# ATMega32U4-CC3000.net
KiCad netlist of a schematic drawn in EAGLE
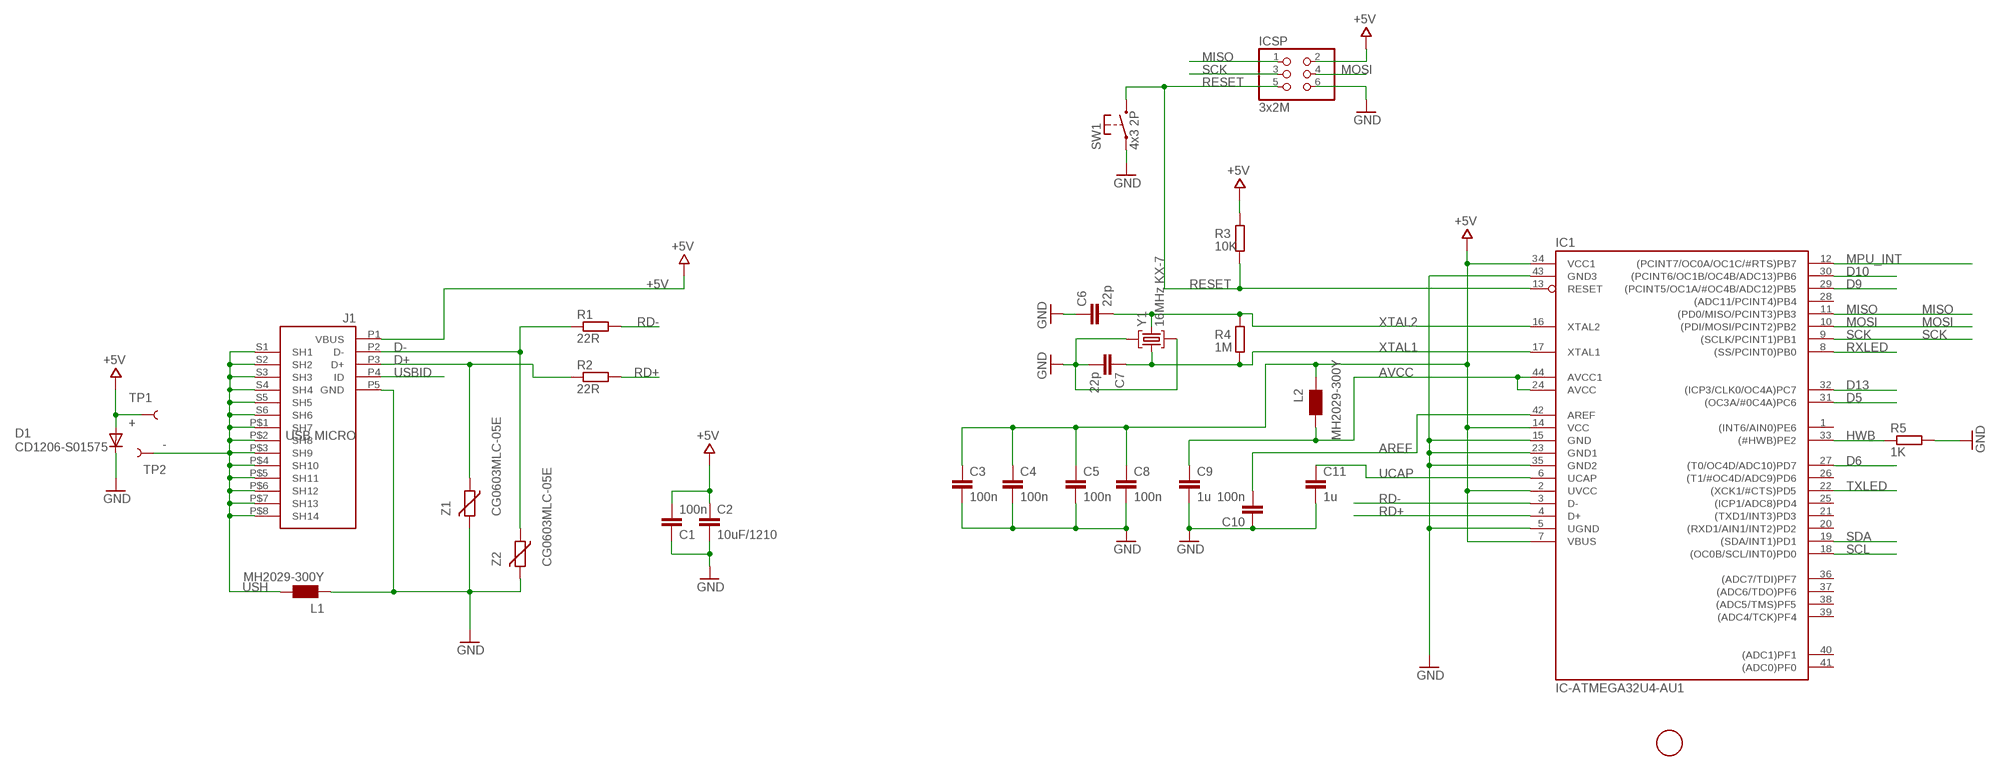
[diagram p0: schematic, sheet 1, part 1 of 2]
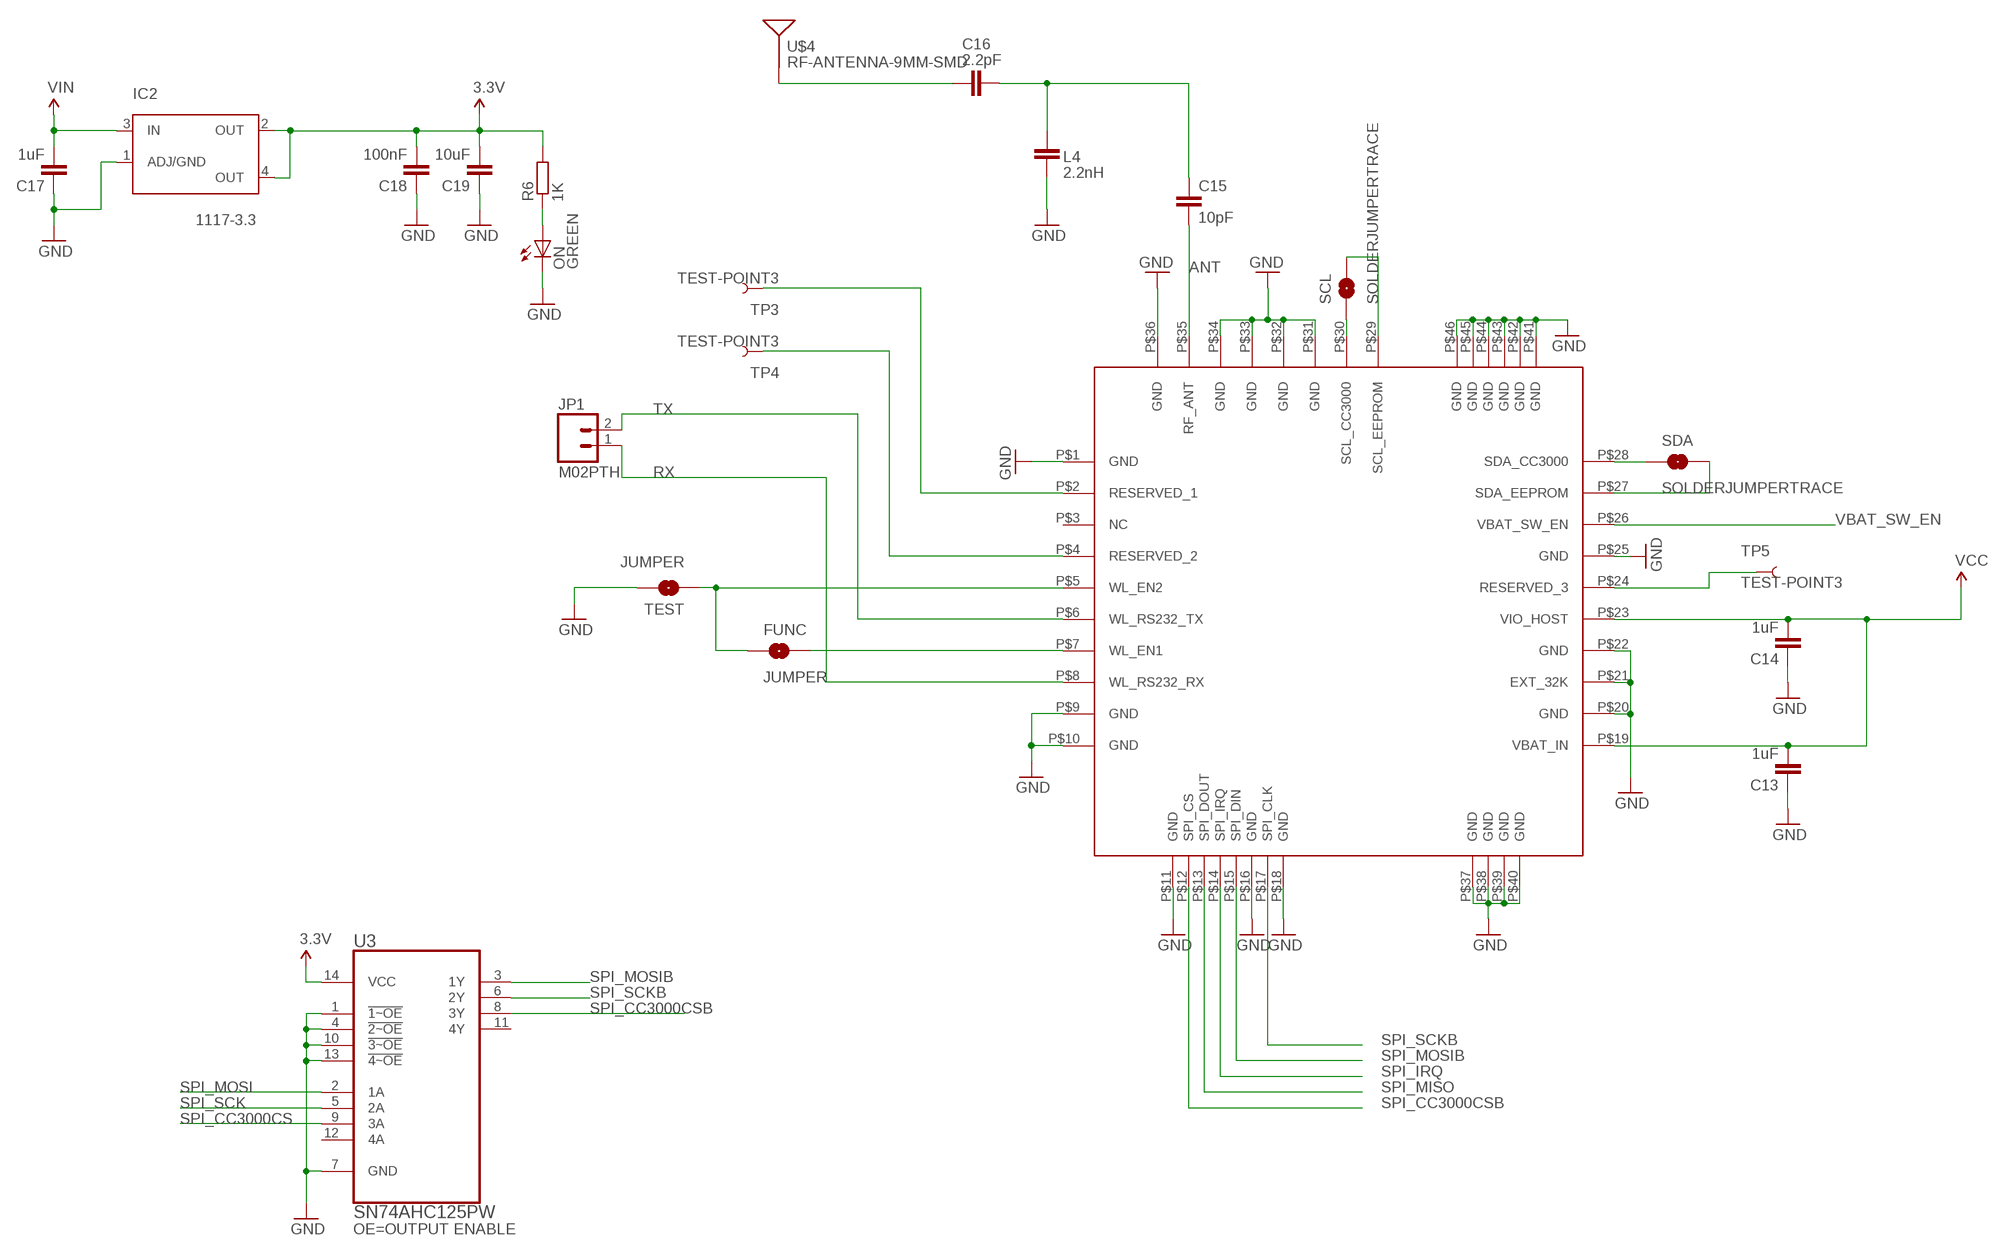
[diagram p1: schematic, sheet 1, part 2 of 2]

(export (version "E")
  (design (tool "Eeschema 10.0.6"))
  (components
    (comp (ref "C1")
      (value "100n")
      (footprint "eagle-import:C0603-ROUND")
      (libsource (lib "eagle-import") (part "C-EUC0603"))
    )
    (comp (ref "C2")
      (value "10uF/1210")
      (footprint "eagle-import:CAP-1210_SMC-B-SMT")
      (libsource (lib "eagle-import") (part "CAPACITOR1210"))
    )
    (comp (ref "C3")
      (value "100n")
      (footprint "eagle-import:CAP-0402-SMT-ROUND")
      (libsource (lib "eagle-import") (part "CAPACITOR0402"))
    )
    (comp (ref "C4")
      (value "100n")
      (footprint "eagle-import:CAP-0402-SMT-ROUND")
      (libsource (lib "eagle-import") (part "CAPACITOR0402"))
    )
    (comp (ref "C5")
      (value "100n")
      (footprint "eagle-import:CAP-0402-SMT-ROUND")
      (libsource (lib "eagle-import") (part "CAPACITOR0402"))
    )
    (comp (ref "C6")
      (value "22p")
      (footprint "eagle-import:CAP-0402-SMT-ROUND")
      (libsource (lib "eagle-import") (part "CAPACITOR0402"))
    )
    (comp (ref "C7")
      (value "22p")
      (footprint "eagle-import:CAP-0402-SMT-ROUND")
      (libsource (lib "eagle-import") (part "CAPACITOR0402"))
    )
    (comp (ref "C8")
      (value "100n")
      (footprint "eagle-import:CAP-0402-SMT-ROUND")
      (libsource (lib "eagle-import") (part "CAPACITOR0402"))
    )
    (comp (ref "C9")
      (value "1u")
      (footprint "eagle-import:CAP-0402-SMT-ROUND")
      (libsource (lib "eagle-import") (part "CAPACITOR0402"))
    )
    (comp (ref "C10")
      (value "100n")
      (footprint "eagle-import:CAP-0402-SMT-ROUND")
      (libsource (lib "eagle-import") (part "CAPACITOR0402"))
    )
    (comp (ref "C11")
      (value "1u")
      (footprint "eagle-import:CAP-0402-SMT-ROUND")
      (libsource (lib "eagle-import") (part "CAPACITOR0402"))
    )
    (comp (ref "C13")
      (value "1uF")
      (footprint "eagle-import:CAP-0603-SMT-ROUND")
      (libsource (lib "eagle-import") (part "CAPACITOR0603"))
    )
    (comp (ref "C14")
      (value "1uF")
      (footprint "eagle-import:CAP-0603-SMT-ROUND")
      (libsource (lib "eagle-import") (part "CAPACITOR0603"))
    )
    (comp (ref "C15")
      (value "10pF")
      (footprint "eagle-import:CAP-0603-SMT-ROUND")
      (libsource (lib "eagle-import") (part "CAPACITOR0603"))
    )
    (comp (ref "C16")
      (value "2.2pF")
      (footprint "eagle-import:CAP-0603-SMT-ROUND")
      (libsource (lib "eagle-import") (part "CAPACITOR0603"))
    )
    (comp (ref "C17")
      (value "1uF")
      (footprint "eagle-import:CAP-0603-SMT-ROUND")
      (libsource (lib "eagle-import") (part "CAPACITOR0603"))
    )
    (comp (ref "C18")
      (value "100nF")
      (footprint "eagle-import:CAP-0603-SMT-ROUND")
      (libsource (lib "eagle-import") (part "CAPACITOR0603"))
    )
    (comp (ref "C19")
      (value "10uF")
      (footprint "eagle-import:CAP-1210_SMC-B-SMT")
      (libsource (lib "eagle-import") (part "CAPACITOR1210"))
    )
    (comp (ref "D1")
      (value "CD1206-S01575")
      (footprint "eagle-import:DIODE-1206-SMT")
      (libsource (lib "eagle-import") (part "DIODE-SWITCHINGCD1206-S01575"))
    )
    (comp (ref "FID1")
      (value "FIDUCIALMOUNT")
      (footprint "eagle-import:FIDUCIA-MOUNT")
      (libsource (lib "eagle-import") (part "FIDUCIALMOUNT"))
    )
    (comp (ref "FUNC")
      (value "JUMPER")
      (footprint "eagle-import:SJ_2S-TRACE")
      (libsource (lib "eagle-import") (part "SparkFun-Passives_SOLDERJUMPERTRACE"))
    )
    (comp (ref "IC1")
      (value "IC-ATMEGA32U4-AU1")
      (footprint "eagle-import:QFP-10X10-44P")
      (libsource (lib "eagle-import") (part "IC-ATMEGA32U4-AU1"))
    )
    (comp (ref "IC2")
      (value "1117-3.3")
      (footprint "eagle-import:LDO-SOT223")
      (libsource (lib "eagle-import") (part "LDO-AMS1117-X"))
    )
    (comp (ref "ICSP")
      (value "3x2M")
      (footprint "eagle-import:2X03")
      (libsource (lib "eagle-import") (part "PINHD-2X3"))
    )
    (comp (ref "J1")
      (value "USB MICRO")
      (footprint "eagle-import:CON2_USB_MICRO_B_AT")
      (libsource (lib "eagle-import") (part "MYCON2_USB-MINI-B"))
    )
    (comp (ref "JP1")
      (value "M02PTH")
      (footprint "eagle-import:1X02")
      (libsource (lib "eagle-import") (part "M02PTH"))
    )
    (comp (ref "L1")
      (value "MH2029-300Y")
      (footprint "eagle-import:0805")
      (libsource (lib "eagle-import") (part "WE-CBF_0805"))
    )
    (comp (ref "L2")
      (value "MH2029-300Y")
      (footprint "eagle-import:0805")
      (libsource (lib "eagle-import") (part "WE-CBF_0805"))
    )
    (comp (ref "L4")
      (value "2.2nH")
      (footprint "eagle-import:CAP-0603-SMT-ROUND")
      (libsource (lib "eagle-import") (part "CAPACITOR0603"))
    )
    (comp (ref "ON")
      (value "GREEN")
      (footprint "eagle-import:LED-0805-SMT")
      (libsource (lib "eagle-import") (part "DIODE-LED0805"))
    )
    (comp (ref "R1")
      (value "22R")
      (footprint "eagle-import:RESISTOR-0402-SMT-ROUND")
      (libsource (lib "eagle-import") (part "RESISTOR0402"))
    )
    (comp (ref "R2")
      (value "22R")
      (footprint "eagle-import:RESISTOR-0402-SMT-ROUND")
      (libsource (lib "eagle-import") (part "RESISTOR0402"))
    )
    (comp (ref "R3")
      (value "10K")
      (footprint "eagle-import:RESISTOR-0402-SMT-ROUND")
      (libsource (lib "eagle-import") (part "RESISTOR0402"))
    )
    (comp (ref "R4")
      (value "1M")
      (footprint "eagle-import:RESISTOR-0402-SMT-ROUND")
      (libsource (lib "eagle-import") (part "RESISTOR0402"))
    )
    (comp (ref "R5")
      (value "1K")
      (footprint "eagle-import:RESISTOR-0402-SMT-ROUND")
      (libsource (lib "eagle-import") (part "RESISTOR0402"))
    )
    (comp (ref "R6")
      (value "1K")
      (footprint "eagle-import:RESISTOR-0603-SMT-ROUND")
      (libsource (lib "eagle-import") (part "RESISTOR0603"))
    )
    (comp (ref "SCL")
      (value "SOLDERJUMPERTRACE")
      (footprint "eagle-import:SJ_2S-TRACE")
      (libsource (lib "eagle-import") (part "SparkFun-Passives_SOLDERJUMPERTRACE"))
    )
    (comp (ref "SDA")
      (value "SOLDERJUMPERTRACE")
      (footprint "eagle-import:SJ_2S-TRACE")
      (libsource (lib "eagle-import") (part "SparkFun-Passives_SOLDERJUMPERTRACE"))
    )
    (comp (ref "SW1")
      (value "4x3 2P")
      (footprint "eagle-import:SWITCH-2.1-SMT")
      (libsource (lib "eagle-import") (part "SWITCH-2P2.1-SMT"))
    )
    (comp (ref "TEST")
      (value "JUMPER")
      (footprint "eagle-import:SJ_2S-NO")
      (libsource (lib "eagle-import") (part "SOLDERJUMPERNO"))
    )
    (comp (ref "TP1")
      (value "+")
      (footprint "eagle-import:PAD.03X.05")
      (libsource (lib "eagle-import") (part "TEST-POINT3X5"))
    )
    (comp (ref "TP2")
      (value "-")
      (footprint "eagle-import:PAD.03X.05")
      (libsource (lib "eagle-import") (part "TEST-POINT3X5"))
    )
    (comp (ref "TP3")
      (value "TEST-POINT3")
      (footprint "eagle-import:PAD.03X.03")
      (libsource (lib "eagle-import") (part "TEST-POINT3"))
    )
    (comp (ref "TP4")
      (value "TEST-POINT3")
      (footprint "eagle-import:PAD.03X.03")
      (libsource (lib "eagle-import") (part "TEST-POINT3"))
    )
    (comp (ref "TP5")
      (value "TEST-POINT3")
      (footprint "eagle-import:PAD.03X.03")
      (libsource (lib "eagle-import") (part "TEST-POINT3"))
    )
    (comp (ref "U$4")
      (value "RF-ANTENNA-9MM-SMD")
      (footprint "eagle-import:RF-ANTENNA-9MM")
      (libsource (lib "eagle-import") (part "RF-ANTENNA-9MM-SMD"))
    )
    (comp (ref "U1")
      (value "CC3000")
      (footprint "eagle-import:CC3000")
      (fields (field (name "AUTHOR") "Matt Bigarani"))
      (libsource (lib "eagle-import") (part "CC3000"))
    )
    (comp (ref "U3")
      (value "SN74AHC125PW")
      (footprint "eagle-import:SOP65P640X120-14N")
      (libsource (lib "eagle-import") (part "IC-TI-SN74AHC125PW"))
    )
    (comp (ref "Y1")
      (value "16MHz KX-7")
      (footprint "eagle-import:CRYSTAL-3.2-2.5")
      (libsource (lib "eagle-import") (part "CRYSTAL-3.2-2.5"))
    )
    (comp (ref "Z1")
      (value "CG0603MLC-05E")
      (footprint "eagle-import:CT_CN0603")
      (libsource (lib "eagle-import") (part "VARISTORCN0603"))
    )
    (comp (ref "Z2")
      (value "CG0603MLC-05E")
      (footprint "eagle-import:CT_CN0603")
      (libsource (lib "eagle-import") (part "VARISTORCN0603"))
    )
  )
  (nets
    (net (code "1") (name "+5V") (class "Default")
      (node (ref "C1") (pin "2") (pinfunction "2_2") (pintype "passive"))
      (node (ref "C2") (pin "+") (pinfunction "1_+") (pintype "passive"))
      (node (ref "C3") (pin "1") (pinfunction "1_1") (pintype "passive"))
      (node (ref "C4") (pin "1") (pinfunction "1_1") (pintype "passive"))
      (node (ref "C5") (pin "1") (pinfunction "1_1") (pintype "passive"))
      (node (ref "C8") (pin "1") (pinfunction "1_1") (pintype "passive"))
      (node (ref "D1") (pin "A") (pinfunction "A_A") (pintype "passive"))
      (node (ref "IC1") (pin "14") (pinfunction "VCC_14") (pintype "power_in"))
      (node (ref "IC1") (pin "2") (pinfunction "UVCC_2") (pintype "power_in"))
      (node (ref "IC1") (pin "34") (pinfunction "VCC1_34") (pintype "power_in"))
      (node (ref "IC1") (pin "7") (pinfunction "VBUS_7") (pintype "input"))
      (node (ref "ICSP") (pin "2") (pinfunction "2_2") (pintype "passive"))
      (node (ref "J1") (pin "P1") (pinfunction "VBUS_P1") (pintype "power_in"))
      (node (ref "L2") (pin "1") (pinfunction "1_1") (pintype "passive"))
      (node (ref "R3") (pin "1") (pinfunction "1_1") (pintype "passive"))
      (node (ref "TP1") (pin "P$1") (pinfunction "1_P$1") (pintype "bidirectional"))
    )
    (net (code "2") (name "/ANT") (class "Default")
      (node (ref "C15") (pin "2") (pinfunction "2_2") (pintype "passive"))
      (node (ref "U1") (pin "P$35") (pinfunction "RF_ANT_P$35") (pintype "bidirectional"))
    )
    (net (code "3") (name "/AREF") (class "Default")
      (node (ref "C10") (pin "2") (pinfunction "2_2") (pintype "passive"))
      (node (ref "IC1") (pin "42") (pinfunction "AREF_42") (pintype "power_in"))
    )
    (net (code "4") (name "/AVCC") (class "Default")
      (node (ref "C9") (pin "1") (pinfunction "1_1") (pintype "passive"))
      (node (ref "IC1") (pin "24") (pinfunction "AVCC_24") (pintype "power_in"))
      (node (ref "IC1") (pin "44") (pinfunction "AVCC1_44") (pintype "power_in"))
      (node (ref "L2") (pin "2") (pinfunction "2_2") (pintype "passive"))
    )
    (net (code "5") (name "/D+") (class "Default")
      (node (ref "J1") (pin "P3") (pinfunction "D+_P3") (pintype "bidirectional"))
      (node (ref "R2") (pin "1") (pinfunction "1_1") (pintype "passive"))
      (node (ref "Z1") (pin "1") (pinfunction "1_1") (pintype "passive"))
    )
    (net (code "6") (name "/D-") (class "Default")
      (node (ref "J1") (pin "P2") (pinfunction "D-_P2") (pintype "bidirectional"))
      (node (ref "R1") (pin "1") (pinfunction "1_1") (pintype "passive"))
      (node (ref "Z2") (pin "1") (pinfunction "1_1") (pintype "passive"))
    )
    (net (code "7") (name "/D5") (class "Default")
      (node (ref "IC1") (pin "31") (pinfunction "(OC3A/#0C4A)PC6_31") (pintype "bidirectional"))
    )
    (net (code "8") (name "/D6") (class "Default")
      (node (ref "IC1") (pin "27") (pinfunction "(T0/OC4D/ADC10)PD7_27") (pintype "bidirectional"))
    )
    (net (code "9") (name "/D9") (class "Default")
      (node (ref "IC1") (pin "29") (pinfunction "(PCINT5/OC1A/#OC4B/ADC12)PB5_29") (pintype "bidirectional"))
    )
    (net (code "10") (name "/D10") (class "Default")
      (node (ref "IC1") (pin "30") (pinfunction "(PCINT6/OC1B/OC4B/ADC13)PB6_30") (pintype "bidirectional"))
    )
    (net (code "11") (name "/D13") (class "Default")
      (node (ref "IC1") (pin "32") (pinfunction "(ICP3/CLK0/OC4A)PC7_32") (pintype "bidirectional"))
    )
    (net (code "12") (name "/HWB") (class "Default")
      (node (ref "IC1") (pin "33") (pinfunction "(#HWB)PE2_33") (pintype "bidirectional"))
      (node (ref "R5") (pin "1") (pinfunction "1_1") (pintype "passive"))
    )
    (net (code "13") (name "/MISO") (class "Default")
      (node (ref "IC1") (pin "11") (pinfunction "(PD0/MISO/PCINT3)PB3_11") (pintype "bidirectional"))
      (node (ref "ICSP") (pin "1") (pinfunction "1_1") (pintype "passive"))
    )
    (net (code "14") (name "/MOSI") (class "Default")
      (node (ref "IC1") (pin "10") (pinfunction "(PDI/MOSI/PCINT2)PB2_10") (pintype "bidirectional"))
      (node (ref "ICSP") (pin "4") (pinfunction "4_4") (pintype "passive"))
    )
    (net (code "15") (name "/MPU_INT") (class "Default")
      (node (ref "IC1") (pin "12") (pinfunction "(PCINT7/OC0A/OC1C/#RTS)PB7_12") (pintype "bidirectional"))
    )
    (net (code "16") (name "/RD+") (class "Default")
      (node (ref "IC1") (pin "4") (pinfunction "D+_4") (pintype "bidirectional"))
      (node (ref "R2") (pin "2") (pinfunction "2_2") (pintype "passive"))
    )
    (net (code "17") (name "/RD-") (class "Default")
      (node (ref "IC1") (pin "3") (pinfunction "D-_3") (pintype "bidirectional"))
      (node (ref "R1") (pin "2") (pinfunction "2_2") (pintype "passive"))
    )
    (net (code "18") (name "/RESET") (class "Default")
      (node (ref "IC1") (pin "13") (pinfunction "RESET_13") (pintype "input"))
      (node (ref "ICSP") (pin "5") (pinfunction "5_5") (pintype "passive"))
      (node (ref "R3") (pin "2") (pinfunction "2_2") (pintype "passive"))
      (node (ref "SW1") (pin "2") (pinfunction "2_2") (pintype "passive"))
    )
    (net (code "19") (name "/RX") (class "Default")
      (node (ref "JP1") (pin "1") (pinfunction "1_1") (pintype "passive"))
      (node (ref "U1") (pin "P$8") (pinfunction "WL_RS232_RX_P$8") (pintype "bidirectional"))
    )
    (net (code "20") (name "/RXLED") (class "Default")
      (node (ref "IC1") (pin "8") (pinfunction "(SS/PCINT0)PB0_8") (pintype "bidirectional"))
    )
    (net (code "21") (name "/SCK") (class "Default")
      (node (ref "IC1") (pin "9") (pinfunction "(SCLK/PCINT1)PB1_9") (pintype "bidirectional"))
      (node (ref "ICSP") (pin "3") (pinfunction "3_3") (pintype "passive"))
    )
    (net (code "22") (name "/SCL") (class "Default")
      (node (ref "IC1") (pin "18") (pinfunction "(OC0B/SCL/INT0)PD0_18") (pintype "bidirectional"))
    )
    (net (code "23") (name "/SDA") (class "Default")
      (node (ref "IC1") (pin "19") (pinfunction "(SDA/INT1)PD1_19") (pintype "bidirectional"))
    )
    (net (code "24") (name "/SPI_CC3000CS") (class "Default")
      (node (ref "U3") (pin "9") (pinfunction "3A_9") (pintype "input"))
    )
    (net (code "25") (name "/SPI_CC3000CSB") (class "Default")
      (node (ref "U1") (pin "P$12") (pinfunction "SPI_CS_P$12") (pintype "bidirectional"))
      (node (ref "U3") (pin "8") (pinfunction "3Y_8") (pintype "output"))
    )
    (net (code "26") (name "/SPI_IRQ") (class "Default")
      (node (ref "U1") (pin "P$14") (pinfunction "SPI_IRQ_P$14") (pintype "bidirectional"))
    )
    (net (code "27") (name "/SPI_MISO") (class "Default")
      (node (ref "U1") (pin "P$13") (pinfunction "SPI_DOUT_P$13") (pintype "bidirectional"))
    )
    (net (code "28") (name "/SPI_MOSI") (class "Default")
      (node (ref "U3") (pin "2") (pinfunction "1A_2") (pintype "input"))
    )
    (net (code "29") (name "/SPI_MOSIB") (class "Default")
      (node (ref "U1") (pin "P$15") (pinfunction "SPI_DIN_P$15") (pintype "bidirectional"))
      (node (ref "U3") (pin "3") (pinfunction "1Y_3") (pintype "output"))
    )
    (net (code "30") (name "/SPI_SCK") (class "Default")
      (node (ref "U3") (pin "5") (pinfunction "2A_5") (pintype "input"))
    )
    (net (code "31") (name "/SPI_SCKB") (class "Default")
      (node (ref "U1") (pin "P$17") (pinfunction "SPI_CLK_P$17") (pintype "bidirectional"))
      (node (ref "U3") (pin "6") (pinfunction "2Y_6") (pintype "output"))
    )
    (net (code "32") (name "/TX") (class "Default")
      (node (ref "JP1") (pin "2") (pinfunction "2_2") (pintype "passive"))
      (node (ref "U1") (pin "P$6") (pinfunction "WL_RS232_TX_P$6") (pintype "bidirectional"))
    )
    (net (code "33") (name "/TXLED") (class "Default")
      (node (ref "IC1") (pin "22") (pinfunction "(XCK1/#CTS)PD5_22") (pintype "bidirectional"))
    )
    (net (code "34") (name "/UCAP") (class "Default")
      (node (ref "C11") (pin "1") (pinfunction "1_1") (pintype "passive"))
      (node (ref "IC1") (pin "6") (pinfunction "UCAP_6") (pintype "passive"))
    )
    (net (code "35") (name "/USBID") (class "Default")
      (node (ref "J1") (pin "P4") (pinfunction "ID_P4") (pintype "bidirectional"))
    )
    (net (code "36") (name "/USH") (class "Default")
      (node (ref "J1") (pin "P$1") (pinfunction "SH7_P$1") (pintype "passive"))
      (node (ref "J1") (pin "P$2") (pinfunction "SH8_P$2") (pintype "passive"))
      (node (ref "J1") (pin "P$3") (pinfunction "SH9_P$3") (pintype "passive"))
      (node (ref "J1") (pin "P$4") (pinfunction "SH10_P$4") (pintype "passive"))
      (node (ref "J1") (pin "P$5") (pinfunction "SH11_P$5") (pintype "passive"))
      (node (ref "J1") (pin "P$6") (pinfunction "SH12_P$6") (pintype "passive"))
      (node (ref "J1") (pin "P$7") (pinfunction "SH13_P$7") (pintype "passive"))
      (node (ref "J1") (pin "P$8") (pinfunction "SH14_P$8") (pintype "passive"))
      (node (ref "J1") (pin "S1") (pinfunction "SH1_S1") (pintype "passive"))
      (node (ref "J1") (pin "S2") (pinfunction "SH2_S2") (pintype "passive"))
      (node (ref "J1") (pin "S3") (pinfunction "SH3_S3") (pintype "passive"))
      (node (ref "J1") (pin "S4") (pinfunction "SH4_S4") (pintype "passive"))
      (node (ref "J1") (pin "S5") (pinfunction "SH5_S5") (pintype "passive"))
      (node (ref "J1") (pin "S6") (pinfunction "SH6_S6") (pintype "passive"))
      (node (ref "L1") (pin "2") (pinfunction "2_2") (pintype "passive"))
      (node (ref "TP2") (pin "P$1") (pinfunction "1_P$1") (pintype "bidirectional"))
    )
    (net (code "37") (name "/VBAT_SW_EN") (class "Default")
      (node (ref "U1") (pin "P$26") (pinfunction "VBAT_SW_EN_P$26") (pintype "bidirectional"))
    )
    (net (code "38") (name "/XTAL1") (class "Default")
      (node (ref "C7") (pin "1") (pinfunction "1_1") (pintype "passive"))
      (node (ref "IC1") (pin "17") (pinfunction "XTAL1_17") (pintype "bidirectional"))
      (node (ref "R4") (pin "1") (pinfunction "1_1") (pintype "passive"))
      (node (ref "Y1") (pin "1") (pinfunction "C1_1") (pintype "passive"))
    )
    (net (code "39") (name "/XTAL2") (class "Default")
      (node (ref "C6") (pin "2") (pinfunction "2_2") (pintype "passive"))
      (node (ref "IC1") (pin "16") (pinfunction "XTAL2_16") (pintype "bidirectional"))
      (node (ref "R4") (pin "2") (pinfunction "2_2") (pintype "passive"))
      (node (ref "Y1") (pin "3") (pinfunction "C2_3") (pintype "passive"))
    )
    (net (code "40") (name "3.3V") (class "Default")
      (node (ref "C13") (pin "2") (pinfunction "2_2") (pintype "passive"))
      (node (ref "C14") (pin "2") (pinfunction "2_2") (pintype "passive"))
      (node (ref "C18") (pin "2") (pinfunction "2_2") (pintype "passive"))
      (node (ref "C19") (pin "-") (pinfunction "2_-") (pintype "passive"))
      (node (ref "IC2") (pin "2") (pinfunction "OUT_2") (pintype "passive"))
      (node (ref "IC2") (pin "4") (pinfunction "OUT_4") (pintype "passive"))
      (node (ref "R6") (pin "2") (pinfunction "2_2") (pintype "passive"))
      (node (ref "U1") (pin "P$19") (pinfunction "VBAT_IN_P$19") (pintype "bidirectional"))
      (node (ref "U1") (pin "P$23") (pinfunction "VIO_HOST_P$23") (pintype "bidirectional"))
      (node (ref "U3") (pin "14") (pinfunction "VCC_14") (pintype "power_in"))
    )
    (net (code "41") (name "GND") (class "Default")
      (node (ref "C1") (pin "1") (pinfunction "1_1") (pintype "passive"))
      (node (ref "C10") (pin "1") (pinfunction "1_1") (pintype "passive"))
      (node (ref "C11") (pin "2") (pinfunction "2_2") (pintype "passive"))
      (node (ref "C13") (pin "1") (pinfunction "1_1") (pintype "passive"))
      (node (ref "C14") (pin "1") (pinfunction "1_1") (pintype "passive"))
      (node (ref "C17") (pin "1") (pinfunction "1_1") (pintype "passive"))
      (node (ref "C18") (pin "1") (pinfunction "1_1") (pintype "passive"))
      (node (ref "C19") (pin "+") (pinfunction "1_+") (pintype "passive"))
      (node (ref "C2") (pin "-") (pinfunction "2_-") (pintype "passive"))
      (node (ref "C3") (pin "2") (pinfunction "2_2") (pintype "passive"))
      (node (ref "C4") (pin "2") (pinfunction "2_2") (pintype "passive"))
      (node (ref "C5") (pin "2") (pinfunction "2_2") (pintype "passive"))
      (node (ref "C6") (pin "1") (pinfunction "1_1") (pintype "passive"))
      (node (ref "C7") (pin "2") (pinfunction "2_2") (pintype "passive"))
      (node (ref "C8") (pin "2") (pinfunction "2_2") (pintype "passive"))
      (node (ref "C9") (pin "2") (pinfunction "2_2") (pintype "passive"))
      (node (ref "D1") (pin "C") (pinfunction "C_C") (pintype "passive"))
      (node (ref "IC1") (pin "15") (pinfunction "GND_15") (pintype "power_in"))
      (node (ref "IC1") (pin "23") (pinfunction "GND1_23") (pintype "power_in"))
      (node (ref "IC1") (pin "35") (pinfunction "GND2_35") (pintype "power_in"))
      (node (ref "IC1") (pin "43") (pinfunction "GND3_43") (pintype "power_in"))
      (node (ref "IC1") (pin "5") (pinfunction "UGND_5") (pintype "power_in"))
      (node (ref "IC2") (pin "1") (pinfunction "ADJ/GND_1") (pintype "input"))
      (node (ref "ICSP") (pin "6") (pinfunction "6_6") (pintype "passive"))
      (node (ref "J1") (pin "P5") (pinfunction "GND_P5") (pintype "passive"))
      (node (ref "L1") (pin "1") (pinfunction "1_1") (pintype "passive"))
      (node (ref "L4") (pin "1") (pinfunction "1_1") (pintype "passive"))
      (node (ref "ON") (pin "C") (pinfunction "C_C") (pintype "passive"))
      (node (ref "R5") (pin "2") (pinfunction "2_2") (pintype "passive"))
      (node (ref "SW1") (pin "1") (pinfunction "1_1") (pintype "passive"))
      (node (ref "TEST") (pin "2") (pinfunction "2_2") (pintype "passive"))
      (node (ref "U1") (pin "P$1") (pinfunction "GND_P$1") (pintype "power_in"))
      (node (ref "U1") (pin "P$10") (pinfunction "GND_P$10") (pintype "power_in"))
      (node (ref "U1") (pin "P$11") (pinfunction "GND_P$11") (pintype "power_in"))
      (node (ref "U1") (pin "P$16") (pinfunction "GND_P$16") (pintype "power_in"))
      (node (ref "U1") (pin "P$18") (pinfunction "GND_P$18") (pintype "power_in"))
      (node (ref "U1") (pin "P$20") (pinfunction "GND_P$20") (pintype "bidirectional"))
      (node (ref "U1") (pin "P$21") (pinfunction "EXT_32K_P$21") (pintype "bidirectional"))
      (node (ref "U1") (pin "P$22") (pinfunction "GND_P$22") (pintype "bidirectional"))
      (node (ref "U1") (pin "P$25") (pinfunction "GND_P$25") (pintype "bidirectional"))
      (node (ref "U1") (pin "P$31") (pinfunction "GND_P$31") (pintype "power_in"))
      (node (ref "U1") (pin "P$32") (pinfunction "GND_P$32") (pintype "power_in"))
      (node (ref "U1") (pin "P$33") (pinfunction "GND_P$33") (pintype "power_in"))
      (node (ref "U1") (pin "P$34") (pinfunction "GND_P$34") (pintype "power_in"))
      (node (ref "U1") (pin "P$36") (pinfunction "GND_P$36") (pintype "passive"))
      (node (ref "U1") (pin "P$37") (pinfunction "GND_P$37") (pintype "power_in"))
      (node (ref "U1") (pin "P$38") (pinfunction "GND_P$38") (pintype "passive"))
      (node (ref "U1") (pin "P$39") (pinfunction "GND_P$39") (pintype "power_in"))
      (node (ref "U1") (pin "P$40") (pinfunction "GND_P$40") (pintype "power_in"))
      (node (ref "U1") (pin "P$41") (pinfunction "GND_P$41") (pintype "power_in"))
      (node (ref "U1") (pin "P$42") (pinfunction "GND_P$42") (pintype "power_in"))
      (node (ref "U1") (pin "P$43") (pinfunction "GND_P$43") (pintype "power_in"))
      (node (ref "U1") (pin "P$44") (pinfunction "GND_P$44") (pintype "power_in"))
      (node (ref "U1") (pin "P$45") (pinfunction "GND_P$45") (pintype "power_in"))
      (node (ref "U1") (pin "P$46") (pinfunction "GND_P$46") (pintype "power_in"))
      (node (ref "U1") (pin "P$9") (pinfunction "GND_P$9") (pintype "bidirectional"))
      (node (ref "U3") (pin "1") (pinfunction "~{1}OE_1") (pintype "input"))
      (node (ref "U3") (pin "10") (pinfunction "~{3}OE_10") (pintype "input"))
      (node (ref "U3") (pin "13") (pinfunction "~{4}OE_13") (pintype "input"))
      (node (ref "U3") (pin "4") (pinfunction "~{2}OE_4") (pintype "input"))
      (node (ref "U3") (pin "7") (pinfunction "GND_7") (pintype "passive"))
      (node (ref "Y1") (pin "2") (pinfunction "GND_2") (pintype "passive"))
      (node (ref "Y1") (pin "4") (pinfunction "GND_4") (pintype "passive"))
      (node (ref "Z1") (pin "2") (pinfunction "2_2") (pintype "passive"))
      (node (ref "Z2") (pin "2") (pinfunction "2_2") (pintype "passive"))
    )
    (net (code "42") (name "Net-(C15-Pad1)") (class "Default")
      (node (ref "C15") (pin "1") (pinfunction "1_1") (pintype "passive"))
      (node (ref "C16") (pin "2") (pinfunction "2_2") (pintype "passive"))
      (node (ref "L4") (pin "2") (pinfunction "2_2") (pintype "passive"))
    )
    (net (code "43") (name "Net-(ON-PadA)") (class "Default")
      (node (ref "ON") (pin "A") (pinfunction "A_A") (pintype "passive"))
      (node (ref "R6") (pin "1") (pinfunction "1_1") (pintype "passive"))
    )
    (net (code "44") (name "Net-(TP3-1)") (class "Default")
      (node (ref "TP3") (pin "P$1") (pinfunction "1_P$1") (pintype "bidirectional"))
      (node (ref "U1") (pin "P$2") (pinfunction "RESERVED_1_P$2") (pintype "bidirectional"))
    )
    (net (code "45") (name "Net-(TP4-1)") (class "Default")
      (node (ref "TP4") (pin "P$1") (pinfunction "1_P$1") (pintype "bidirectional"))
      (node (ref "U1") (pin "P$4") (pinfunction "RESERVED_2_P$4") (pintype "bidirectional"))
    )
    (net (code "46") (name "Net-(TP5-1)") (class "Default")
      (node (ref "TP5") (pin "P$1") (pinfunction "1_P$1") (pintype "bidirectional"))
      (node (ref "U1") (pin "P$24") (pinfunction "RESERVED_3_P$24") (pintype "bidirectional"))
    )
    (net (code "47") (name "Net-(U$4-SIGNAL)") (class "Default")
      (node (ref "C16") (pin "1") (pinfunction "1_1") (pintype "passive"))
      (node (ref "U$4") (pin "SIG") (pinfunction "SIGNAL_SIG") (pintype "bidirectional"))
    )
    (net (code "48") (name "Net-(U1-SCL_CC3000)") (class "Default")
      (node (ref "SCL") (pin "1") (pinfunction "1_1") (pintype "passive"))
      (node (ref "U1") (pin "P$30") (pinfunction "SCL_CC3000_P$30") (pintype "power_in"))
    )
    (net (code "49") (name "Net-(U1-SCL_EEPROM)") (class "Default")
      (node (ref "SCL") (pin "2") (pinfunction "2_2") (pintype "passive"))
      (node (ref "U1") (pin "P$29") (pinfunction "SCL_EEPROM_P$29") (pintype "power_in"))
    )
    (net (code "50") (name "Net-(U1-SDA_CC3000)") (class "Default")
      (node (ref "SDA") (pin "1") (pinfunction "1_1") (pintype "passive"))
      (node (ref "U1") (pin "P$28") (pinfunction "SDA_CC3000_P$28") (pintype "bidirectional"))
    )
    (net (code "51") (name "Net-(U1-SDA_EEPROM)") (class "Default")
      (node (ref "SDA") (pin "2") (pinfunction "2_2") (pintype "passive"))
      (node (ref "U1") (pin "P$27") (pinfunction "SDA_EEPROM_P$27") (pintype "bidirectional"))
    )
    (net (code "52") (name "Net-(U1-WL_EN1)") (class "Default")
      (node (ref "FUNC") (pin "2") (pinfunction "2_2") (pintype "passive"))
      (node (ref "U1") (pin "P$7") (pinfunction "WL_EN1_P$7") (pintype "bidirectional"))
    )
    (net (code "53") (name "Net-(U1-WL_EN2)") (class "Default")
      (node (ref "FUNC") (pin "1") (pinfunction "1_1") (pintype "passive"))
      (node (ref "TEST") (pin "1") (pinfunction "1_1") (pintype "passive"))
      (node (ref "U1") (pin "P$5") (pinfunction "WL_EN2_P$5") (pintype "bidirectional"))
    )
    (net (code "54") (name "VIN") (class "Default")
      (node (ref "C17") (pin "2") (pinfunction "2_2") (pintype "passive"))
      (node (ref "IC2") (pin "3") (pinfunction "IN_3") (pintype "input"))
    )
    (net (code "55") (name "unconnected-(IC1-(ADC0)PF0-Pad41)") (class "Default")
      (node (ref "IC1") (pin "41") (pinfunction "(ADC0)PF0_41") (pintype "bidirectional"))
    )
    (net (code "56") (name "unconnected-(IC1-(ADC1)PF1-Pad40)") (class "Default")
      (node (ref "IC1") (pin "40") (pinfunction "(ADC1)PF1_40") (pintype "bidirectional"))
    )
    (net (code "57") (name "unconnected-(IC1-(ADC4{slash}TCK)PF4-Pad39)") (class "Default")
      (node (ref "IC1") (pin "39") (pinfunction "(ADC4/TCK)PF4_39") (pintype "bidirectional"))
    )
    (net (code "58") (name "unconnected-(IC1-(ADC5{slash}TMS)PF5-Pad38)") (class "Default")
      (node (ref "IC1") (pin "38") (pinfunction "(ADC5/TMS)PF5_38") (pintype "bidirectional"))
    )
    (net (code "59") (name "unconnected-(IC1-(ADC6{slash}TDO)PF6-Pad37)") (class "Default")
      (node (ref "IC1") (pin "37") (pinfunction "(ADC6/TDO)PF6_37") (pintype "bidirectional"))
    )
    (net (code "60") (name "unconnected-(IC1-(ADC7{slash}TDI)PF7-Pad36)") (class "Default")
      (node (ref "IC1") (pin "36") (pinfunction "(ADC7/TDI)PF7_36") (pintype "bidirectional"))
    )
    (net (code "61") (name "unconnected-(IC1-(ADC11{slash}PCINT4)PB4-Pad28)") (class "Default")
      (node (ref "IC1") (pin "28") (pinfunction "(ADC11/PCINT4)PB4_28") (pintype "bidirectional"))
    )
    (net (code "62") (name "unconnected-(IC1-(ICP1{slash}ADC8)PD4-Pad25)") (class "Default")
      (node (ref "IC1") (pin "25") (pinfunction "(ICP1/ADC8)PD4_25") (pintype "bidirectional"))
    )
    (net (code "63") (name "unconnected-(IC1-(INT6{slash}AIN0)PE6-Pad1)") (class "Default")
      (node (ref "IC1") (pin "1") (pinfunction "(INT6/AIN0)PE6_1") (pintype "bidirectional"))
    )
    (net (code "64") (name "unconnected-(IC1-(RXD1{slash}AIN1{slash}INT2)PD2-Pad20)") (class "Default")
      (node (ref "IC1") (pin "20") (pinfunction "(RXD1/AIN1/INT2)PD2_20") (pintype "bidirectional"))
    )
    (net (code "65") (name "unconnected-(IC1-(T1{slash}#OC4D{slash}ADC9)PD6-Pad26)") (class "Default")
      (node (ref "IC1") (pin "26") (pinfunction "(T1/#OC4D/ADC9)PD6_26") (pintype "bidirectional"))
    )
    (net (code "66") (name "unconnected-(IC1-(TXD1{slash}INT3)PD3-Pad21)") (class "Default")
      (node (ref "IC1") (pin "21") (pinfunction "(TXD1/INT3)PD3_21") (pintype "bidirectional"))
    )
    (net (code "67") (name "unconnected-(U1-NC-PadP$3)") (class "Default")
      (node (ref "U1") (pin "P$3") (pinfunction "NC_P$3") (pintype "no_connect"))
    )
    (net (code "68") (name "unconnected-(U3-4A-Pad12)") (class "Default")
      (node (ref "U3") (pin "12") (pinfunction "4A_12") (pintype "input"))
    )
    (net (code "69") (name "unconnected-(U3-4Y-Pad11)") (class "Default")
      (node (ref "U3") (pin "11") (pinfunction "4Y_11") (pintype "output"))
    )
  )
)
